# digAudio-PLT133.net
KiCad netlist of a schematic drawn in EAGLE
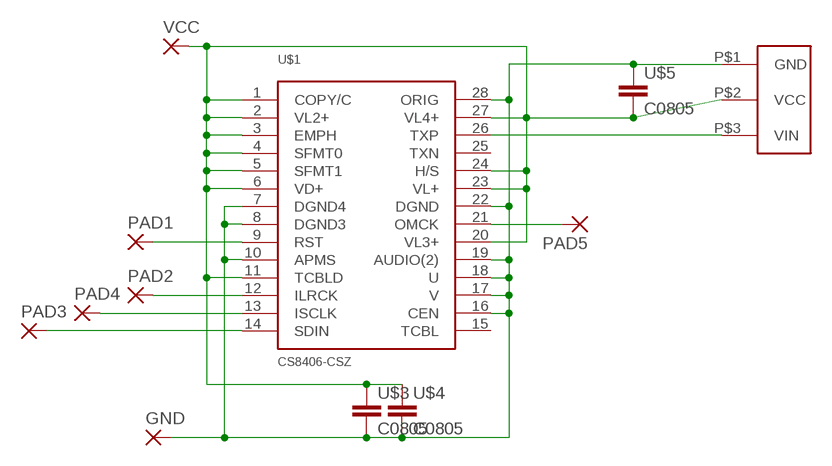
[diagram p0: schematic, sheet 1]

(export (version "E")
  (design (tool "Eeschema 10.0.6"))
  (components
    (comp (ref "GND")
      (value "SMD2")
      (footprint "eagle-import:SMD1,27-2,54")
      (libsource (lib "eagle-import") (part "SMD2"))
    )
    (comp (ref "PAD1")
      (value "SMD2")
      (footprint "eagle-import:SMD1,27-2,54")
      (libsource (lib "eagle-import") (part "SMD2"))
    )
    (comp (ref "PAD2")
      (value "SMD2")
      (footprint "eagle-import:SMD1,27-2,54")
      (libsource (lib "eagle-import") (part "SMD2"))
    )
    (comp (ref "PAD3")
      (value "SMD2")
      (footprint "eagle-import:SMD1,27-2,54")
      (libsource (lib "eagle-import") (part "SMD2"))
    )
    (comp (ref "PAD4")
      (value "SMD2")
      (footprint "eagle-import:SMD1,27-2,54")
      (libsource (lib "eagle-import") (part "SMD2"))
    )
    (comp (ref "PAD5")
      (value "SMD2")
      (footprint "eagle-import:SMD1,27-2,54")
      (libsource (lib "eagle-import") (part "SMD2"))
    )
    (comp (ref "U$1")
      (value "CS8406-CSZ")
      (footprint "eagle-import:SO28W")
      (libsource (lib "eagle-import") (part "CS8406-CSZ"))
    )
    (comp (ref "U$3")
      (value "C0805")
      (footprint "eagle-import:Z0805")
      (libsource (lib "eagle-import") (part "C0805"))
    )
    (comp (ref "U$4")
      (value "C0805")
      (footprint "eagle-import:Z0805")
      (libsource (lib "eagle-import") (part "C0805"))
    )
    (comp (ref "U$5")
      (value "C0805")
      (footprint "eagle-import:Z0805")
      (libsource (lib "eagle-import") (part "C0805"))
    )
    (comp (ref "U$6")
      (value "PLT133/T10W")
      (footprint "eagle-import:PLT133_T10W")
      (libsource (lib "eagle-import") (part "PLT133/T10W"))
    )
    (comp (ref "VCC")
      (value "SMD2")
      (footprint "eagle-import:SMD1,27-2,54")
      (libsource (lib "eagle-import") (part "SMD2"))
    )
  )
  (nets
    (net (code "1") (name "Net-(GND-P)") (class "Default")
      (node (ref "GND") (pin "1") (pinfunction "P_1") (pintype "passive"))
      (node (ref "U$1") (pin "10") (pinfunction "APMS_10") (pintype "bidirectional"))
      (node (ref "U$1") (pin "16") (pinfunction "CEN_16") (pintype "bidirectional"))
      (node (ref "U$1") (pin "17") (pinfunction "V_17") (pintype "bidirectional"))
      (node (ref "U$1") (pin "18") (pinfunction "U_18") (pintype "bidirectional"))
      (node (ref "U$1") (pin "19") (pinfunction "AUDIO(2)_19") (pintype "bidirectional"))
      (node (ref "U$1") (pin "22") (pinfunction "DGND_22") (pintype "bidirectional"))
      (node (ref "U$1") (pin "28") (pinfunction "ORIG_28") (pintype "bidirectional"))
      (node (ref "U$1") (pin "7") (pinfunction "DGND4_7") (pintype "bidirectional"))
      (node (ref "U$1") (pin "8") (pinfunction "DGND3_8") (pintype "bidirectional"))
      (node (ref "U$3") (pin "2") (pinfunction "2_2") (pintype "passive"))
      (node (ref "U$4") (pin "2") (pinfunction "2_2") (pintype "passive"))
      (node (ref "U$5") (pin "1") (pinfunction "1_1") (pintype "passive"))
      (node (ref "U$6") (pin "P$1") (pinfunction "GND_P$1") (pintype "bidirectional"))
    )
    (net (code "2") (name "Net-(PAD1-P)") (class "Default")
      (node (ref "PAD1") (pin "1") (pinfunction "P_1") (pintype "passive"))
      (node (ref "U$1") (pin "9") (pinfunction "RST_9") (pintype "bidirectional"))
    )
    (net (code "3") (name "Net-(PAD2-P)") (class "Default")
      (node (ref "PAD2") (pin "1") (pinfunction "P_1") (pintype "passive"))
      (node (ref "U$1") (pin "12") (pinfunction "ILRCK_12") (pintype "bidirectional"))
    )
    (net (code "4") (name "Net-(PAD3-P)") (class "Default")
      (node (ref "PAD3") (pin "1") (pinfunction "P_1") (pintype "passive"))
      (node (ref "U$1") (pin "14") (pinfunction "SDIN_14") (pintype "bidirectional"))
    )
    (net (code "5") (name "Net-(PAD4-P)") (class "Default")
      (node (ref "PAD4") (pin "1") (pinfunction "P_1") (pintype "passive"))
      (node (ref "U$1") (pin "13") (pinfunction "ISCLK_13") (pintype "bidirectional"))
    )
    (net (code "6") (name "Net-(PAD5-P)") (class "Default")
      (node (ref "PAD5") (pin "1") (pinfunction "P_1") (pintype "passive"))
      (node (ref "U$1") (pin "21") (pinfunction "OMCK_21") (pintype "bidirectional"))
    )
    (net (code "7") (name "Net-(U$1-COPY{slash}C)") (class "Default")
      (node (ref "U$1") (pin "1") (pinfunction "COPY/C_1") (pintype "bidirectional"))
      (node (ref "U$1") (pin "11") (pinfunction "TCBLD_11") (pintype "bidirectional"))
      (node (ref "U$1") (pin "2") (pinfunction "VL2+_2") (pintype "bidirectional"))
      (node (ref "U$1") (pin "20") (pinfunction "VL3+_20") (pintype "bidirectional"))
      (node (ref "U$1") (pin "23") (pinfunction "VL+_23") (pintype "bidirectional"))
      (node (ref "U$1") (pin "24") (pinfunction "H/S_24") (pintype "bidirectional"))
      (node (ref "U$1") (pin "27") (pinfunction "VL4+_27") (pintype "bidirectional"))
      (node (ref "U$1") (pin "3") (pinfunction "EMPH_3") (pintype "bidirectional"))
      (node (ref "U$1") (pin "4") (pinfunction "SFMT0_4") (pintype "bidirectional"))
      (node (ref "U$1") (pin "5") (pinfunction "SFMT1_5") (pintype "bidirectional"))
      (node (ref "U$1") (pin "6") (pinfunction "VD+_6") (pintype "bidirectional"))
      (node (ref "U$3") (pin "1") (pinfunction "1_1") (pintype "passive"))
      (node (ref "U$4") (pin "1") (pinfunction "1_1") (pintype "passive"))
      (node (ref "U$5") (pin "2") (pinfunction "2_2") (pintype "passive"))
      (node (ref "U$6") (pin "P$2") (pinfunction "VCC_P$2") (pintype "bidirectional"))
      (node (ref "VCC") (pin "1") (pinfunction "P_1") (pintype "passive"))
    )
    (net (code "8") (name "Net-(U$1-TXP)") (class "Default")
      (node (ref "U$1") (pin "26") (pinfunction "TXP_26") (pintype "bidirectional"))
      (node (ref "U$6") (pin "P$3") (pinfunction "VIN_P$3") (pintype "bidirectional"))
    )
    (net (code "9") (name "unconnected-(U$1-TCBL-Pad15)") (class "Default")
      (node (ref "U$1") (pin "15") (pinfunction "TCBL_15") (pintype "bidirectional"))
    )
    (net (code "10") (name "unconnected-(U$1-TXN-Pad25)") (class "Default")
      (node (ref "U$1") (pin "25") (pinfunction "TXN_25") (pintype "bidirectional"))
    )
  )
)
